# Relay_PWR_Sheet.net
KiCad netlist of a schematic drawn in Altium Designer
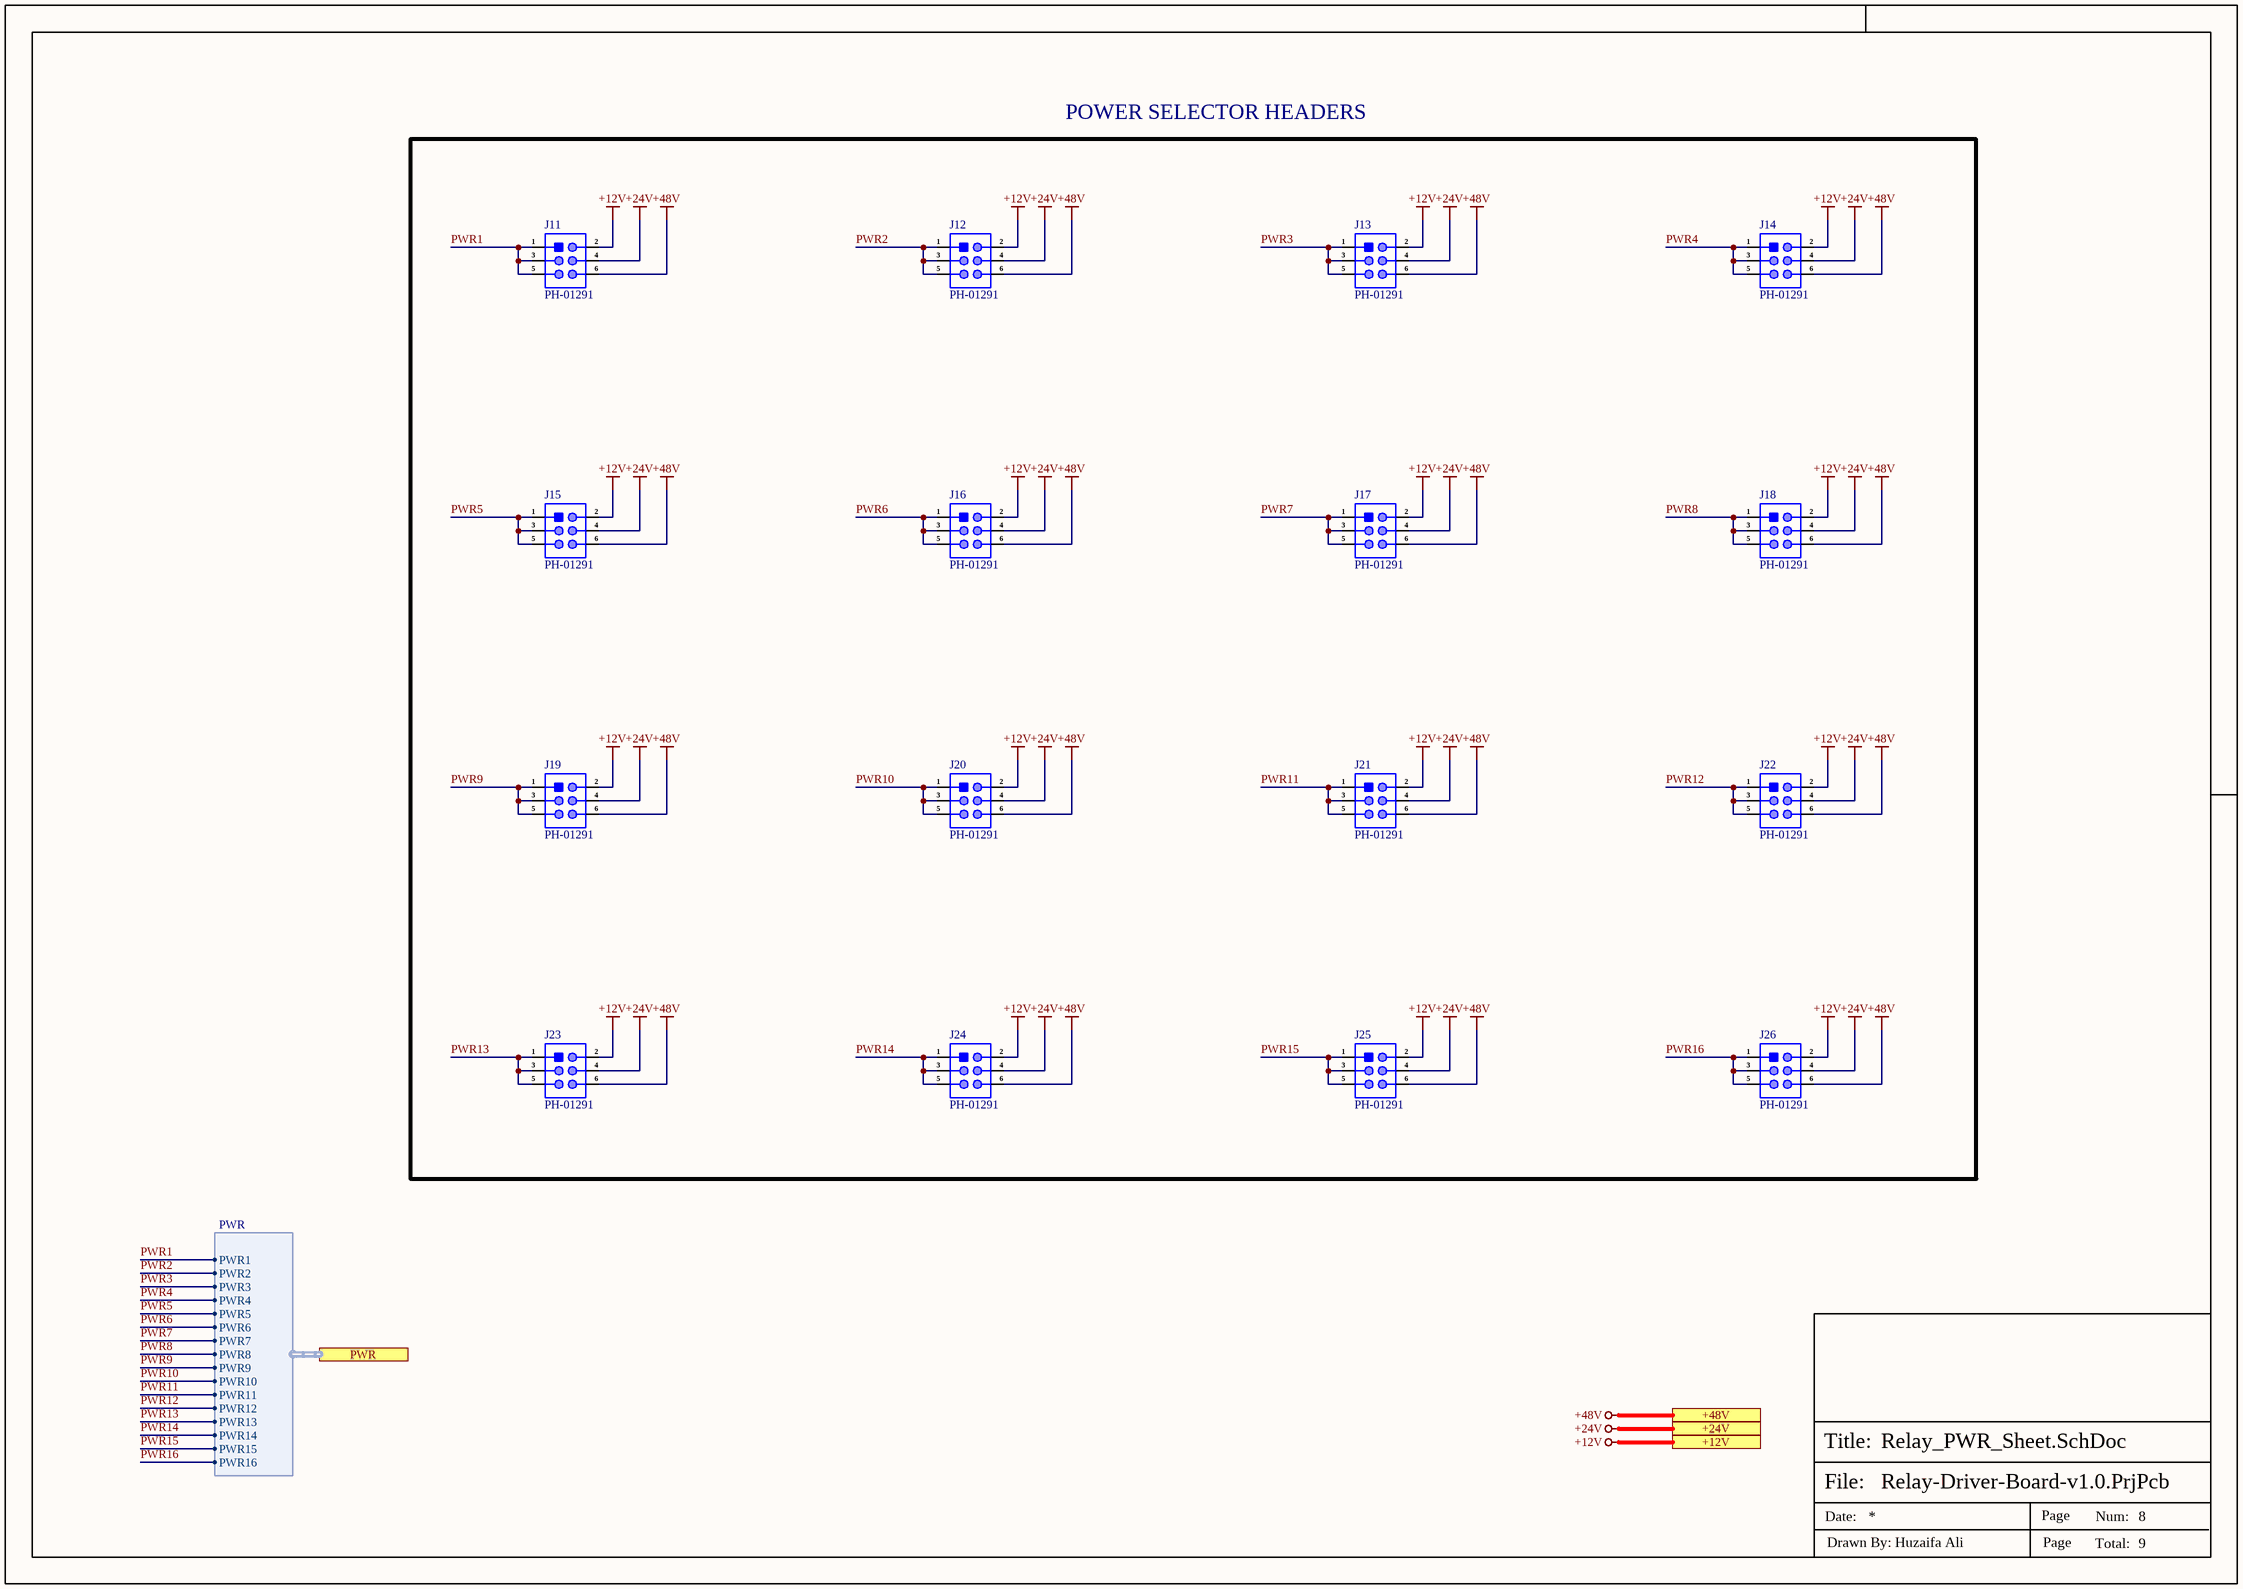
[diagram p0: Relay_PWR_Sheet.SchDoc]

(export (version "E")
  (design (tool "Eeschema 10.0.6"))
  (components
    (comp (ref "J11")
      (value "PH-01291")
      (footprint "PH-01291")
      (fields (field (name "MANUFACTURER") "Liansheng") (field (name "LCSC PART NO") "C2685197"))
      (libsource (lib "eSpark Libraries") (part "PH-01291"))
    )
    (comp (ref "J12")
      (value "PH-01291")
      (footprint "PH-01291")
      (fields (field (name "MANUFACTURER") "Liansheng") (field (name "LCSC PART NO") "C2685197"))
      (libsource (lib "eSpark Libraries") (part "PH-01291"))
    )
    (comp (ref "J13")
      (value "PH-01291")
      (footprint "PH-01291")
      (fields (field (name "MANUFACTURER") "Liansheng") (field (name "LCSC PART NO") "C2685197"))
      (libsource (lib "eSpark Libraries") (part "PH-01291"))
    )
    (comp (ref "J14")
      (value "PH-01291")
      (footprint "PH-01291")
      (fields (field (name "MANUFACTURER") "Liansheng") (field (name "LCSC PART NO") "C2685197"))
      (libsource (lib "eSpark Libraries") (part "PH-01291"))
    )
    (comp (ref "J15")
      (value "PH-01291")
      (footprint "PH-01291")
      (fields (field (name "MANUFACTURER") "Liansheng") (field (name "LCSC PART NO") "C2685197"))
      (libsource (lib "eSpark Libraries") (part "PH-01291"))
    )
    (comp (ref "J16")
      (value "PH-01291")
      (footprint "PH-01291")
      (fields (field (name "MANUFACTURER") "Liansheng") (field (name "LCSC PART NO") "C2685197"))
      (libsource (lib "eSpark Libraries") (part "PH-01291"))
    )
    (comp (ref "J17")
      (value "PH-01291")
      (footprint "PH-01291")
      (fields (field (name "MANUFACTURER") "Liansheng") (field (name "LCSC PART NO") "C2685197"))
      (libsource (lib "eSpark Libraries") (part "PH-01291"))
    )
    (comp (ref "J18")
      (value "PH-01291")
      (footprint "PH-01291")
      (fields (field (name "MANUFACTURER") "Liansheng") (field (name "LCSC PART NO") "C2685197"))
      (libsource (lib "eSpark Libraries") (part "PH-01291"))
    )
    (comp (ref "J19")
      (value "PH-01291")
      (footprint "PH-01291")
      (fields (field (name "MANUFACTURER") "Liansheng") (field (name "LCSC PART NO") "C2685197"))
      (libsource (lib "eSpark Libraries") (part "PH-01291"))
    )
    (comp (ref "J20")
      (value "PH-01291")
      (footprint "PH-01291")
      (fields (field (name "MANUFACTURER") "Liansheng") (field (name "LCSC PART NO") "C2685197"))
      (libsource (lib "eSpark Libraries") (part "PH-01291"))
    )
    (comp (ref "J21")
      (value "PH-01291")
      (footprint "PH-01291")
      (fields (field (name "MANUFACTURER") "Liansheng") (field (name "LCSC PART NO") "C2685197"))
      (libsource (lib "eSpark Libraries") (part "PH-01291"))
    )
    (comp (ref "J22")
      (value "PH-01291")
      (footprint "PH-01291")
      (fields (field (name "MANUFACTURER") "Liansheng") (field (name "LCSC PART NO") "C2685197"))
      (libsource (lib "eSpark Libraries") (part "PH-01291"))
    )
    (comp (ref "J23")
      (value "PH-01291")
      (footprint "PH-01291")
      (fields (field (name "MANUFACTURER") "Liansheng") (field (name "LCSC PART NO") "C2685197"))
      (libsource (lib "eSpark Libraries") (part "PH-01291"))
    )
    (comp (ref "J24")
      (value "PH-01291")
      (footprint "PH-01291")
      (fields (field (name "MANUFACTURER") "Liansheng") (field (name "LCSC PART NO") "C2685197"))
      (libsource (lib "eSpark Libraries") (part "PH-01291"))
    )
    (comp (ref "J25")
      (value "PH-01291")
      (footprint "PH-01291")
      (fields (field (name "MANUFACTURER") "Liansheng") (field (name "LCSC PART NO") "C2685197"))
      (libsource (lib "eSpark Libraries") (part "PH-01291"))
    )
    (comp (ref "J26")
      (value "PH-01291")
      (footprint "PH-01291")
      (fields (field (name "MANUFACTURER") "Liansheng") (field (name "LCSC PART NO") "C2685197"))
      (libsource (lib "eSpark Libraries") (part "PH-01291"))
    )
  )
  (nets
    (net (code "2") (name "+12V") (class "Default")
      (node (ref "J11") (pin "2") (pinfunction "2_2") (pintype "passive"))
      (node (ref "J12") (pin "2") (pinfunction "2_2") (pintype "passive"))
      (node (ref "J13") (pin "2") (pinfunction "2_2") (pintype "passive"))
      (node (ref "J14") (pin "2") (pinfunction "2_2") (pintype "passive"))
      (node (ref "J15") (pin "2") (pinfunction "2_2") (pintype "passive"))
      (node (ref "J16") (pin "2") (pinfunction "2_2") (pintype "passive"))
      (node (ref "J17") (pin "2") (pinfunction "2_2") (pintype "passive"))
      (node (ref "J18") (pin "2") (pinfunction "2_2") (pintype "passive"))
      (node (ref "J19") (pin "2") (pinfunction "2_2") (pintype "passive"))
      (node (ref "J20") (pin "2") (pinfunction "2_2") (pintype "passive"))
      (node (ref "J21") (pin "2") (pinfunction "2_2") (pintype "passive"))
      (node (ref "J22") (pin "2") (pinfunction "2_2") (pintype "passive"))
      (node (ref "J23") (pin "2") (pinfunction "2_2") (pintype "passive"))
      (node (ref "J24") (pin "2") (pinfunction "2_2") (pintype "passive"))
      (node (ref "J25") (pin "2") (pinfunction "2_2") (pintype "passive"))
      (node (ref "J26") (pin "2") (pinfunction "2_2") (pintype "passive"))
    )
    (net (code "3") (name "+24V") (class "Default")
      (node (ref "J11") (pin "4") (pinfunction "4_4") (pintype "passive"))
      (node (ref "J12") (pin "4") (pinfunction "4_4") (pintype "passive"))
      (node (ref "J13") (pin "4") (pinfunction "4_4") (pintype "passive"))
      (node (ref "J14") (pin "4") (pinfunction "4_4") (pintype "passive"))
      (node (ref "J15") (pin "4") (pinfunction "4_4") (pintype "passive"))
      (node (ref "J16") (pin "4") (pinfunction "4_4") (pintype "passive"))
      (node (ref "J17") (pin "4") (pinfunction "4_4") (pintype "passive"))
      (node (ref "J18") (pin "4") (pinfunction "4_4") (pintype "passive"))
      (node (ref "J19") (pin "4") (pinfunction "4_4") (pintype "passive"))
      (node (ref "J20") (pin "4") (pinfunction "4_4") (pintype "passive"))
      (node (ref "J21") (pin "4") (pinfunction "4_4") (pintype "passive"))
      (node (ref "J22") (pin "4") (pinfunction "4_4") (pintype "passive"))
      (node (ref "J23") (pin "4") (pinfunction "4_4") (pintype "passive"))
      (node (ref "J24") (pin "4") (pinfunction "4_4") (pintype "passive"))
      (node (ref "J25") (pin "4") (pinfunction "4_4") (pintype "passive"))
      (node (ref "J26") (pin "4") (pinfunction "4_4") (pintype "passive"))
    )
    (net (code "4") (name "+48V") (class "Default")
      (node (ref "J11") (pin "6") (pinfunction "6_6") (pintype "passive"))
      (node (ref "J12") (pin "6") (pinfunction "6_6") (pintype "passive"))
      (node (ref "J13") (pin "6") (pinfunction "6_6") (pintype "passive"))
      (node (ref "J14") (pin "6") (pinfunction "6_6") (pintype "passive"))
      (node (ref "J15") (pin "6") (pinfunction "6_6") (pintype "passive"))
      (node (ref "J16") (pin "6") (pinfunction "6_6") (pintype "passive"))
      (node (ref "J17") (pin "6") (pinfunction "6_6") (pintype "passive"))
      (node (ref "J18") (pin "6") (pinfunction "6_6") (pintype "passive"))
      (node (ref "J19") (pin "6") (pinfunction "6_6") (pintype "passive"))
      (node (ref "J20") (pin "6") (pinfunction "6_6") (pintype "passive"))
      (node (ref "J21") (pin "6") (pinfunction "6_6") (pintype "passive"))
      (node (ref "J22") (pin "6") (pinfunction "6_6") (pintype "passive"))
      (node (ref "J23") (pin "6") (pinfunction "6_6") (pintype "passive"))
      (node (ref "J24") (pin "6") (pinfunction "6_6") (pintype "passive"))
      (node (ref "J25") (pin "6") (pinfunction "6_6") (pintype "passive"))
      (node (ref "J26") (pin "6") (pinfunction "6_6") (pintype "passive"))
    )
    (net (code "5") (name "/PWR1") (class "Default")
      (node (ref "J11") (pin "1") (pinfunction "1_1") (pintype "passive"))
      (node (ref "J11") (pin "3") (pinfunction "3_3") (pintype "passive"))
      (node (ref "J11") (pin "5") (pinfunction "5_5") (pintype "passive"))
    )
    (net (code "6") (name "/PWR2") (class "Default")
      (node (ref "J12") (pin "1") (pinfunction "1_1") (pintype "passive"))
      (node (ref "J12") (pin "3") (pinfunction "3_3") (pintype "passive"))
      (node (ref "J12") (pin "5") (pinfunction "5_5") (pintype "passive"))
    )
    (net (code "7") (name "/PWR3") (class "Default")
      (node (ref "J13") (pin "1") (pinfunction "1_1") (pintype "passive"))
      (node (ref "J13") (pin "3") (pinfunction "3_3") (pintype "passive"))
      (node (ref "J13") (pin "5") (pinfunction "5_5") (pintype "passive"))
    )
    (net (code "8") (name "/PWR4") (class "Default")
      (node (ref "J14") (pin "1") (pinfunction "1_1") (pintype "passive"))
      (node (ref "J14") (pin "3") (pinfunction "3_3") (pintype "passive"))
      (node (ref "J14") (pin "5") (pinfunction "5_5") (pintype "passive"))
    )
    (net (code "9") (name "/PWR5") (class "Default")
      (node (ref "J15") (pin "1") (pinfunction "1_1") (pintype "passive"))
      (node (ref "J15") (pin "3") (pinfunction "3_3") (pintype "passive"))
      (node (ref "J15") (pin "5") (pinfunction "5_5") (pintype "passive"))
    )
    (net (code "10") (name "/PWR6") (class "Default")
      (node (ref "J16") (pin "1") (pinfunction "1_1") (pintype "passive"))
      (node (ref "J16") (pin "3") (pinfunction "3_3") (pintype "passive"))
      (node (ref "J16") (pin "5") (pinfunction "5_5") (pintype "passive"))
    )
    (net (code "11") (name "/PWR7") (class "Default")
      (node (ref "J17") (pin "1") (pinfunction "1_1") (pintype "passive"))
      (node (ref "J17") (pin "3") (pinfunction "3_3") (pintype "passive"))
      (node (ref "J17") (pin "5") (pinfunction "5_5") (pintype "passive"))
    )
    (net (code "12") (name "/PWR8") (class "Default")
      (node (ref "J18") (pin "1") (pinfunction "1_1") (pintype "passive"))
      (node (ref "J18") (pin "3") (pinfunction "3_3") (pintype "passive"))
      (node (ref "J18") (pin "5") (pinfunction "5_5") (pintype "passive"))
    )
    (net (code "13") (name "/PWR9") (class "Default")
      (node (ref "J19") (pin "1") (pinfunction "1_1") (pintype "passive"))
      (node (ref "J19") (pin "3") (pinfunction "3_3") (pintype "passive"))
      (node (ref "J19") (pin "5") (pinfunction "5_5") (pintype "passive"))
    )
    (net (code "14") (name "/PWR10") (class "Default")
      (node (ref "J20") (pin "1") (pinfunction "1_1") (pintype "passive"))
      (node (ref "J20") (pin "3") (pinfunction "3_3") (pintype "passive"))
      (node (ref "J20") (pin "5") (pinfunction "5_5") (pintype "passive"))
    )
    (net (code "15") (name "/PWR11") (class "Default")
      (node (ref "J21") (pin "1") (pinfunction "1_1") (pintype "passive"))
      (node (ref "J21") (pin "3") (pinfunction "3_3") (pintype "passive"))
      (node (ref "J21") (pin "5") (pinfunction "5_5") (pintype "passive"))
    )
    (net (code "16") (name "/PWR12") (class "Default")
      (node (ref "J22") (pin "1") (pinfunction "1_1") (pintype "passive"))
      (node (ref "J22") (pin "3") (pinfunction "3_3") (pintype "passive"))
      (node (ref "J22") (pin "5") (pinfunction "5_5") (pintype "passive"))
    )
    (net (code "17") (name "/PWR13") (class "Default")
      (node (ref "J23") (pin "1") (pinfunction "1_1") (pintype "passive"))
      (node (ref "J23") (pin "3") (pinfunction "3_3") (pintype "passive"))
      (node (ref "J23") (pin "5") (pinfunction "5_5") (pintype "passive"))
    )
    (net (code "18") (name "/PWR14") (class "Default")
      (node (ref "J24") (pin "1") (pinfunction "1_1") (pintype "passive"))
      (node (ref "J24") (pin "3") (pinfunction "3_3") (pintype "passive"))
      (node (ref "J24") (pin "5") (pinfunction "5_5") (pintype "passive"))
    )
    (net (code "19") (name "/PWR15") (class "Default")
      (node (ref "J25") (pin "1") (pinfunction "1_1") (pintype "passive"))
      (node (ref "J25") (pin "3") (pinfunction "3_3") (pintype "passive"))
      (node (ref "J25") (pin "5") (pinfunction "5_5") (pintype "passive"))
    )
    (net (code "20") (name "/PWR16") (class "Default")
      (node (ref "J26") (pin "1") (pinfunction "1_1") (pintype "passive"))
      (node (ref "J26") (pin "3") (pinfunction "3_3") (pintype "passive"))
      (node (ref "J26") (pin "5") (pinfunction "5_5") (pintype "passive"))
    )
  )
)
